# S7CAS-PLEIADES-CARTE-MERE_P06_ETHERNET.net
KiCad netlist of a schematic drawn in Altium Designer
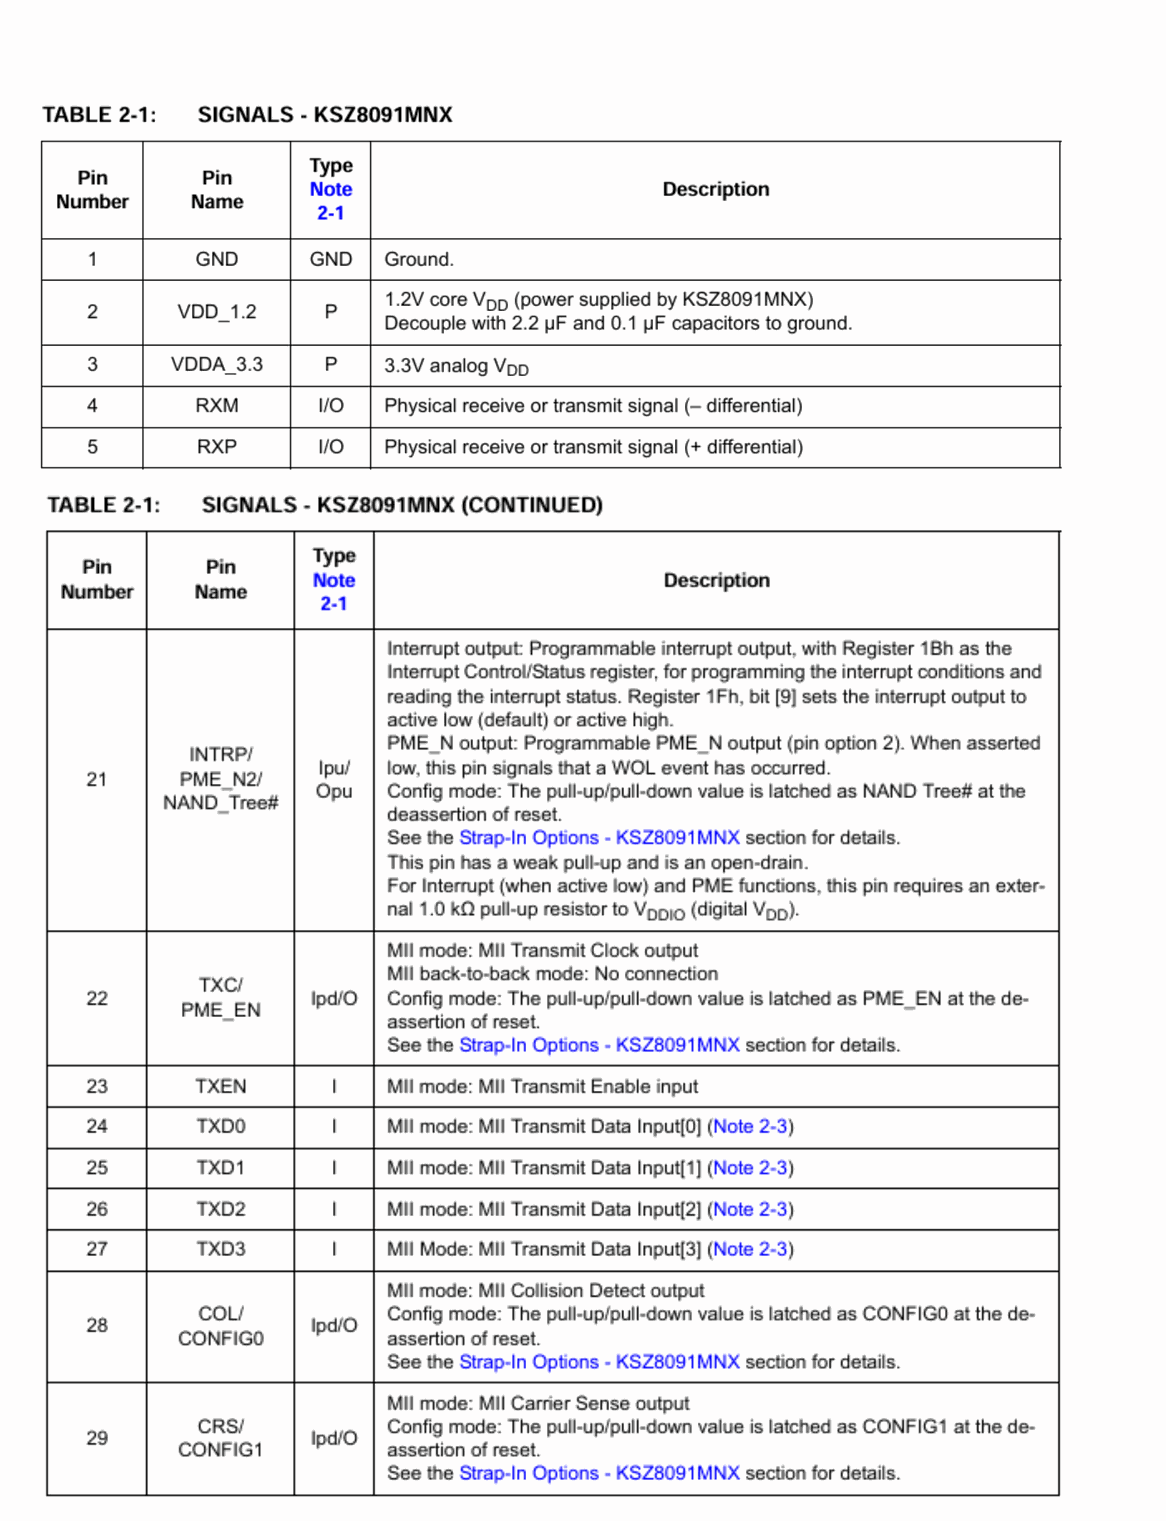
[diagram p0: S7CAS-PLEIADES-CARTE-MERE_P06_ETHERNET.SCHDOC, top left]
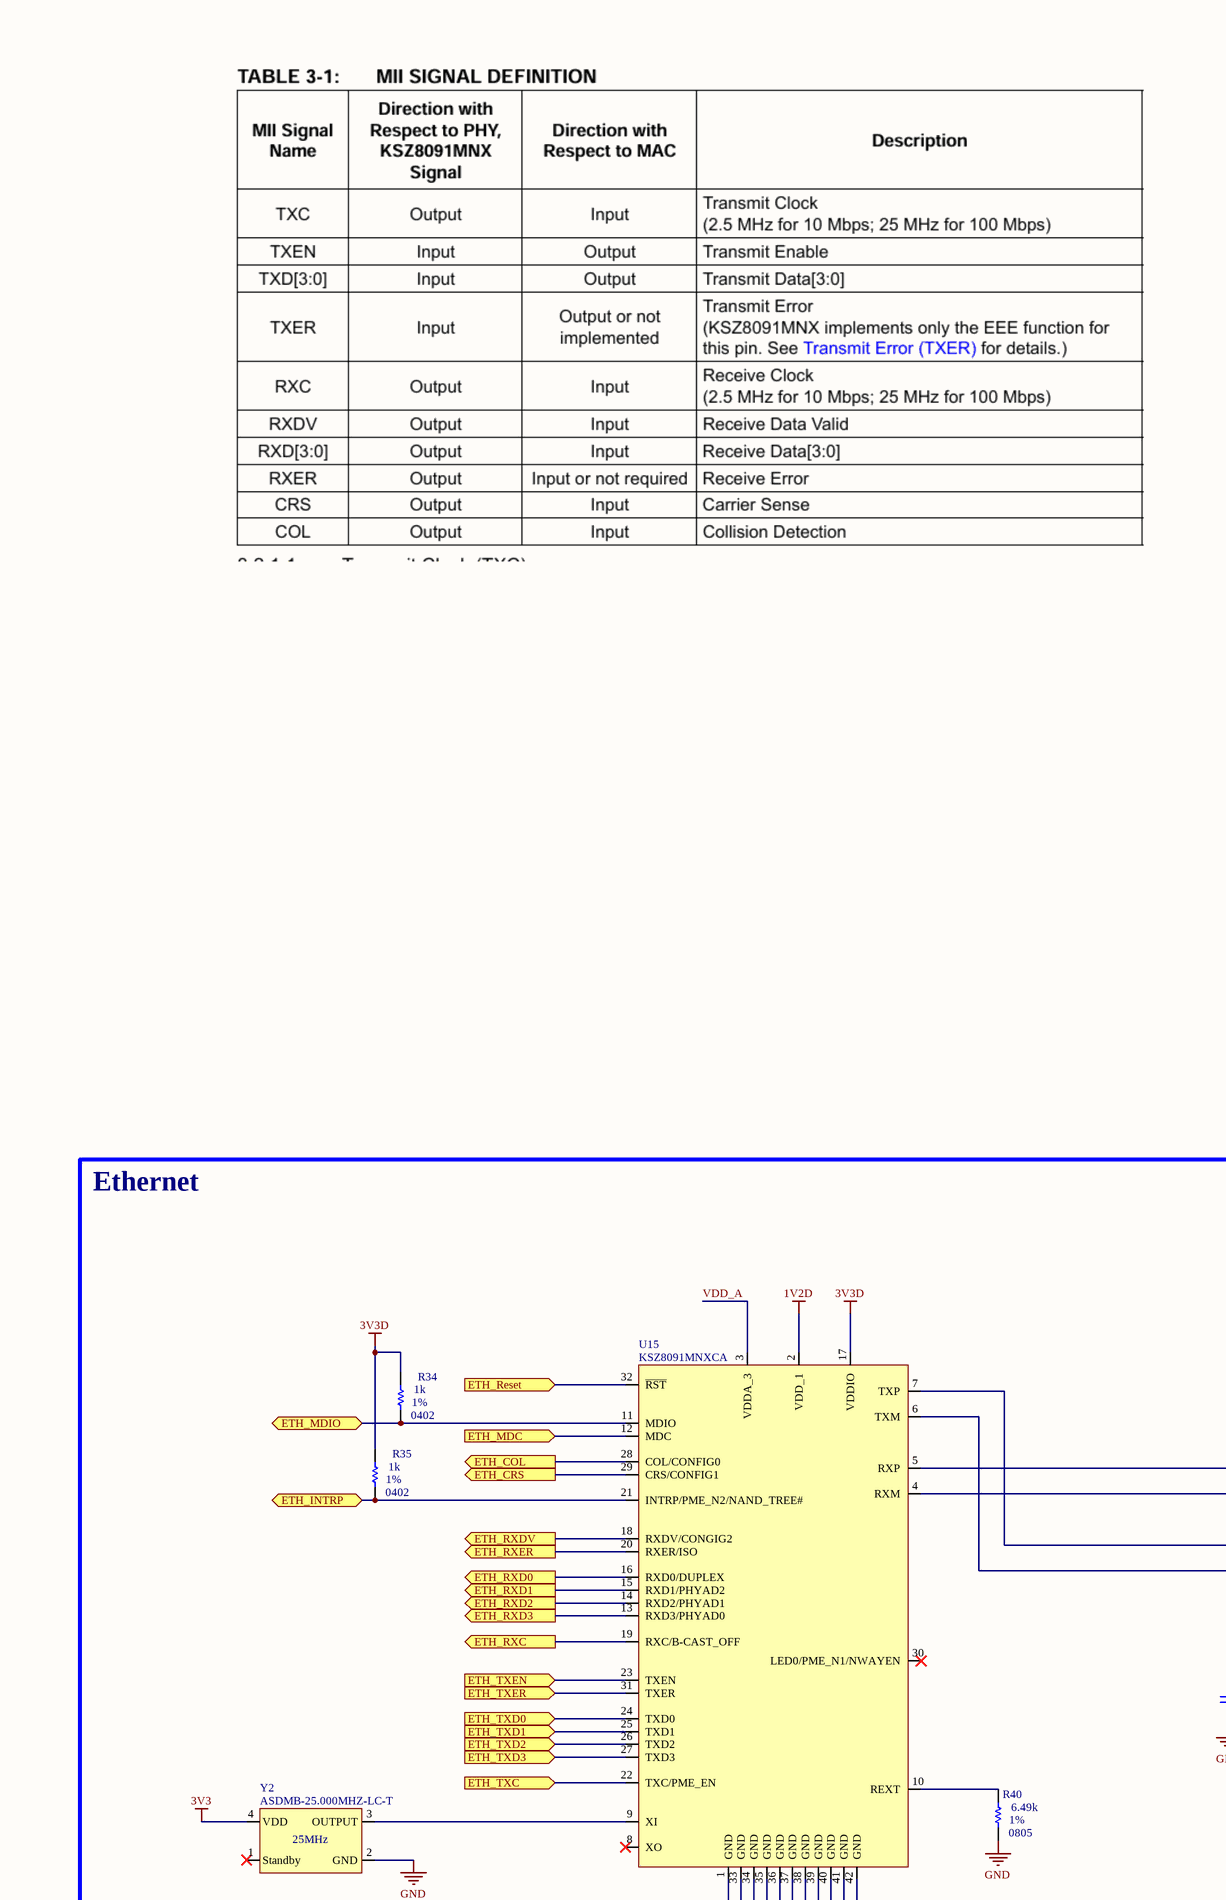
[diagram p1: S7CAS-PLEIADES-CARTE-MERE_P06_ETHERNET.SCHDOC, top middle]
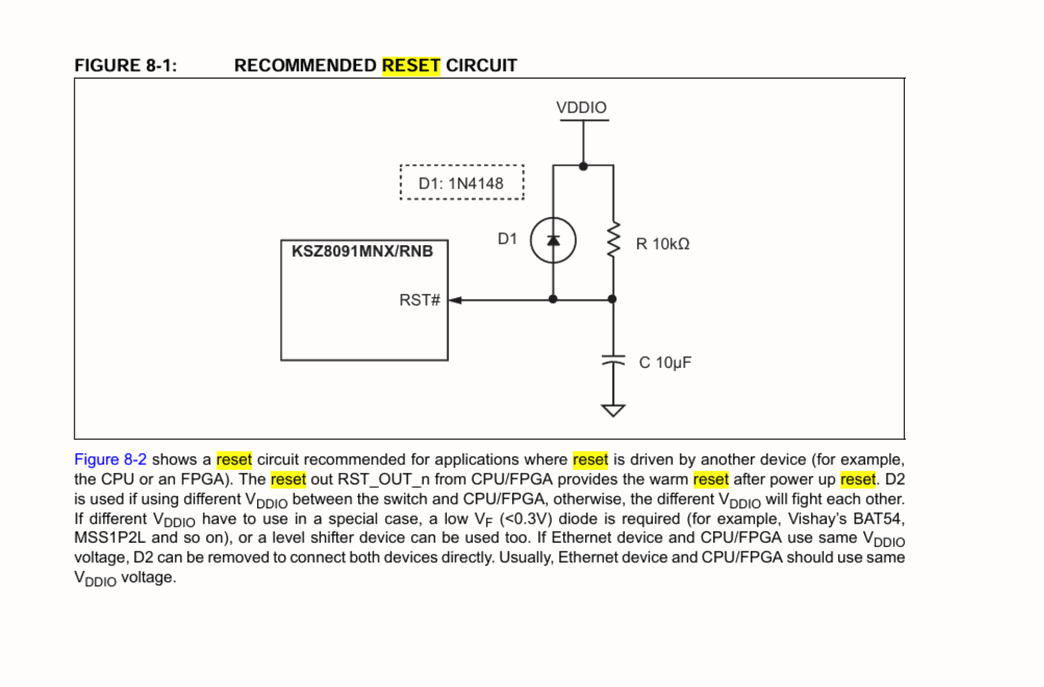
[diagram p2: S7CAS-PLEIADES-CARTE-MERE_P06_ETHERNET.SCHDOC, top right]
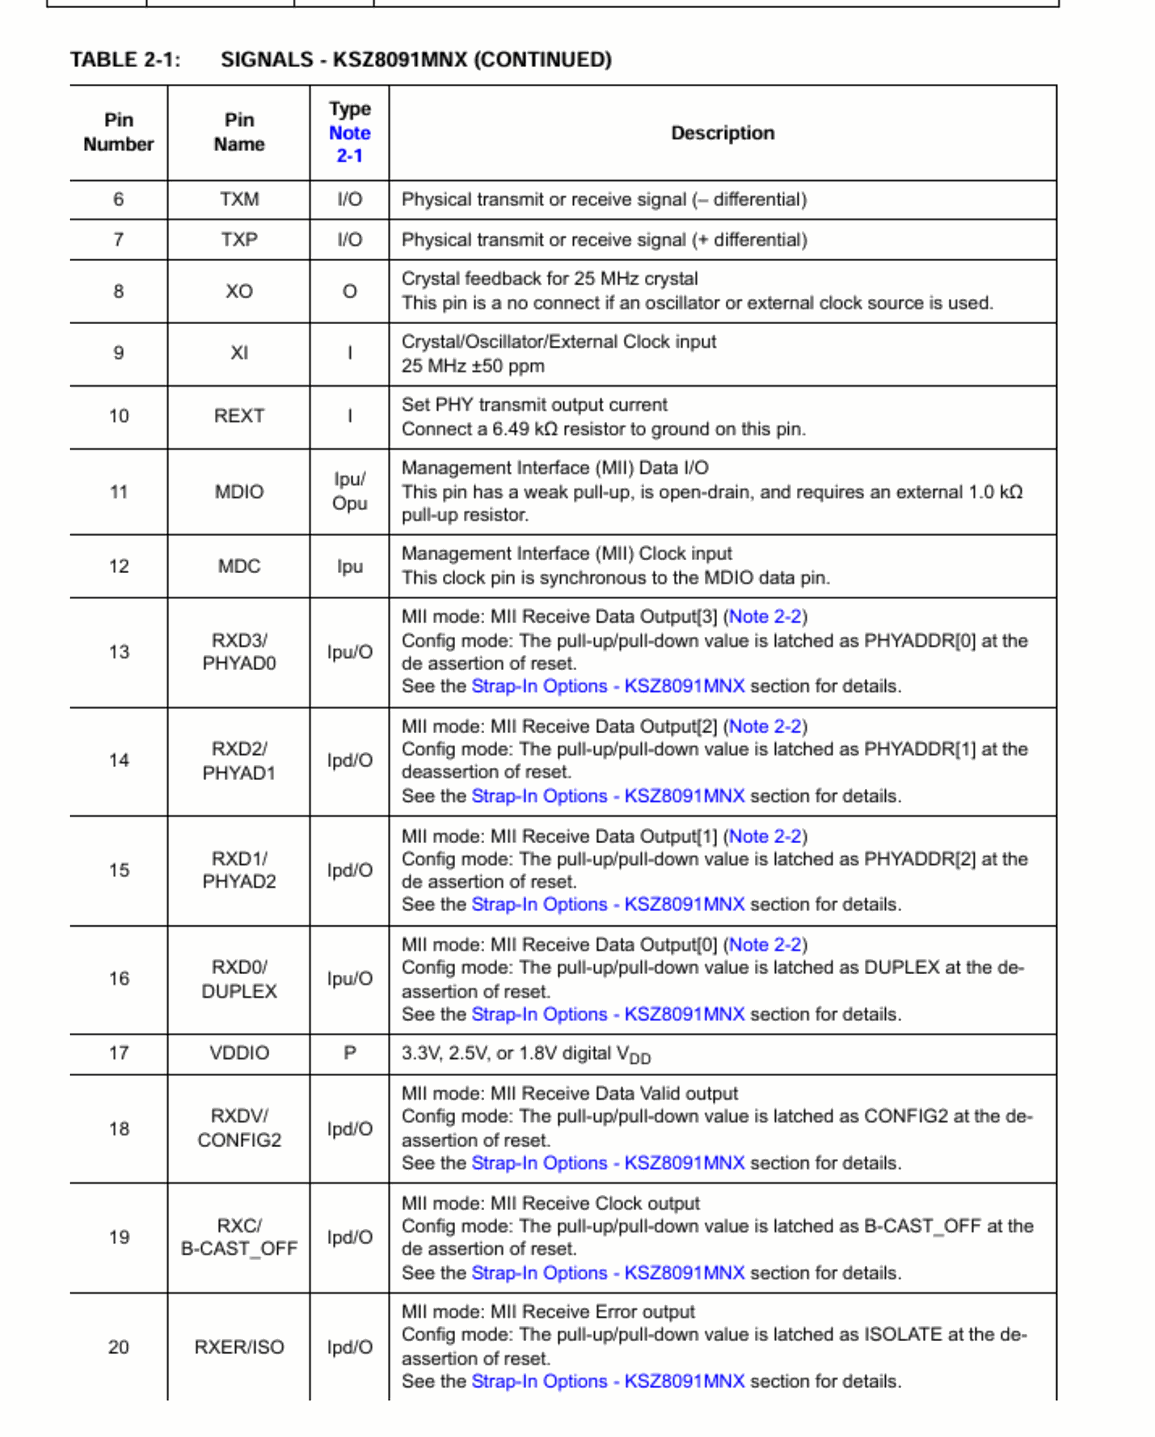
[diagram p3: S7CAS-PLEIADES-CARTE-MERE_P06_ETHERNET.SCHDOC, bottom left]
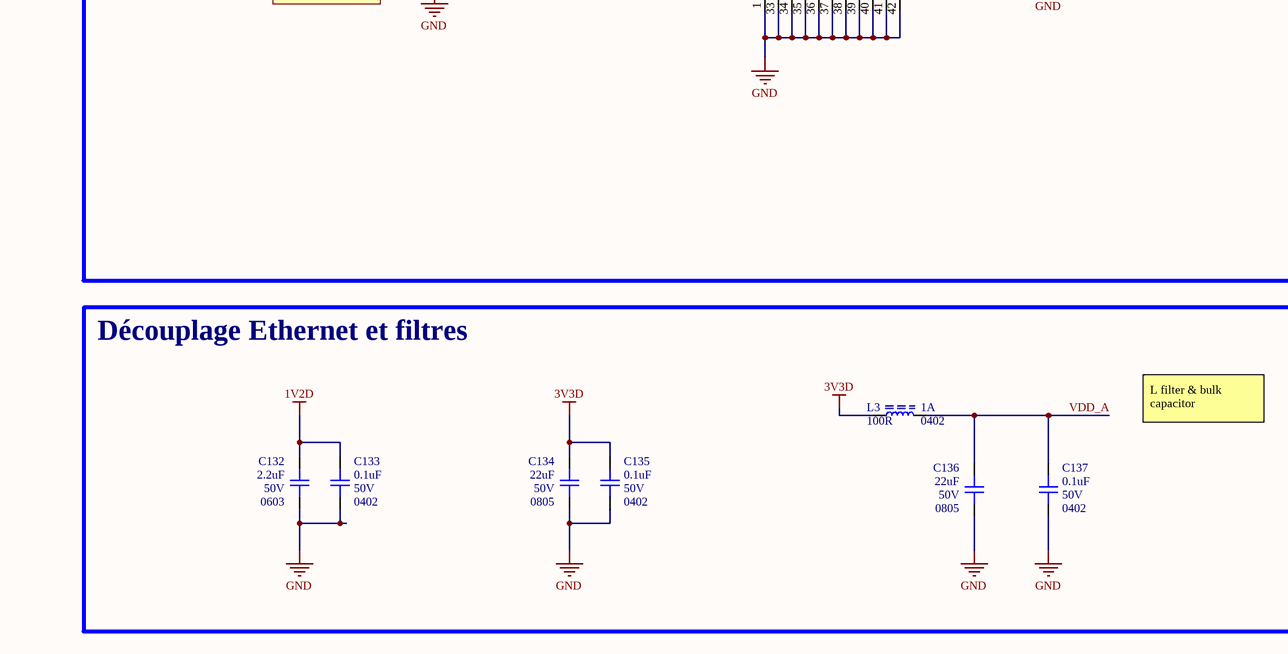
[diagram p4: S7CAS-PLEIADES-CARTE-MERE_P06_ETHERNET.SCHDOC, bottom middle]
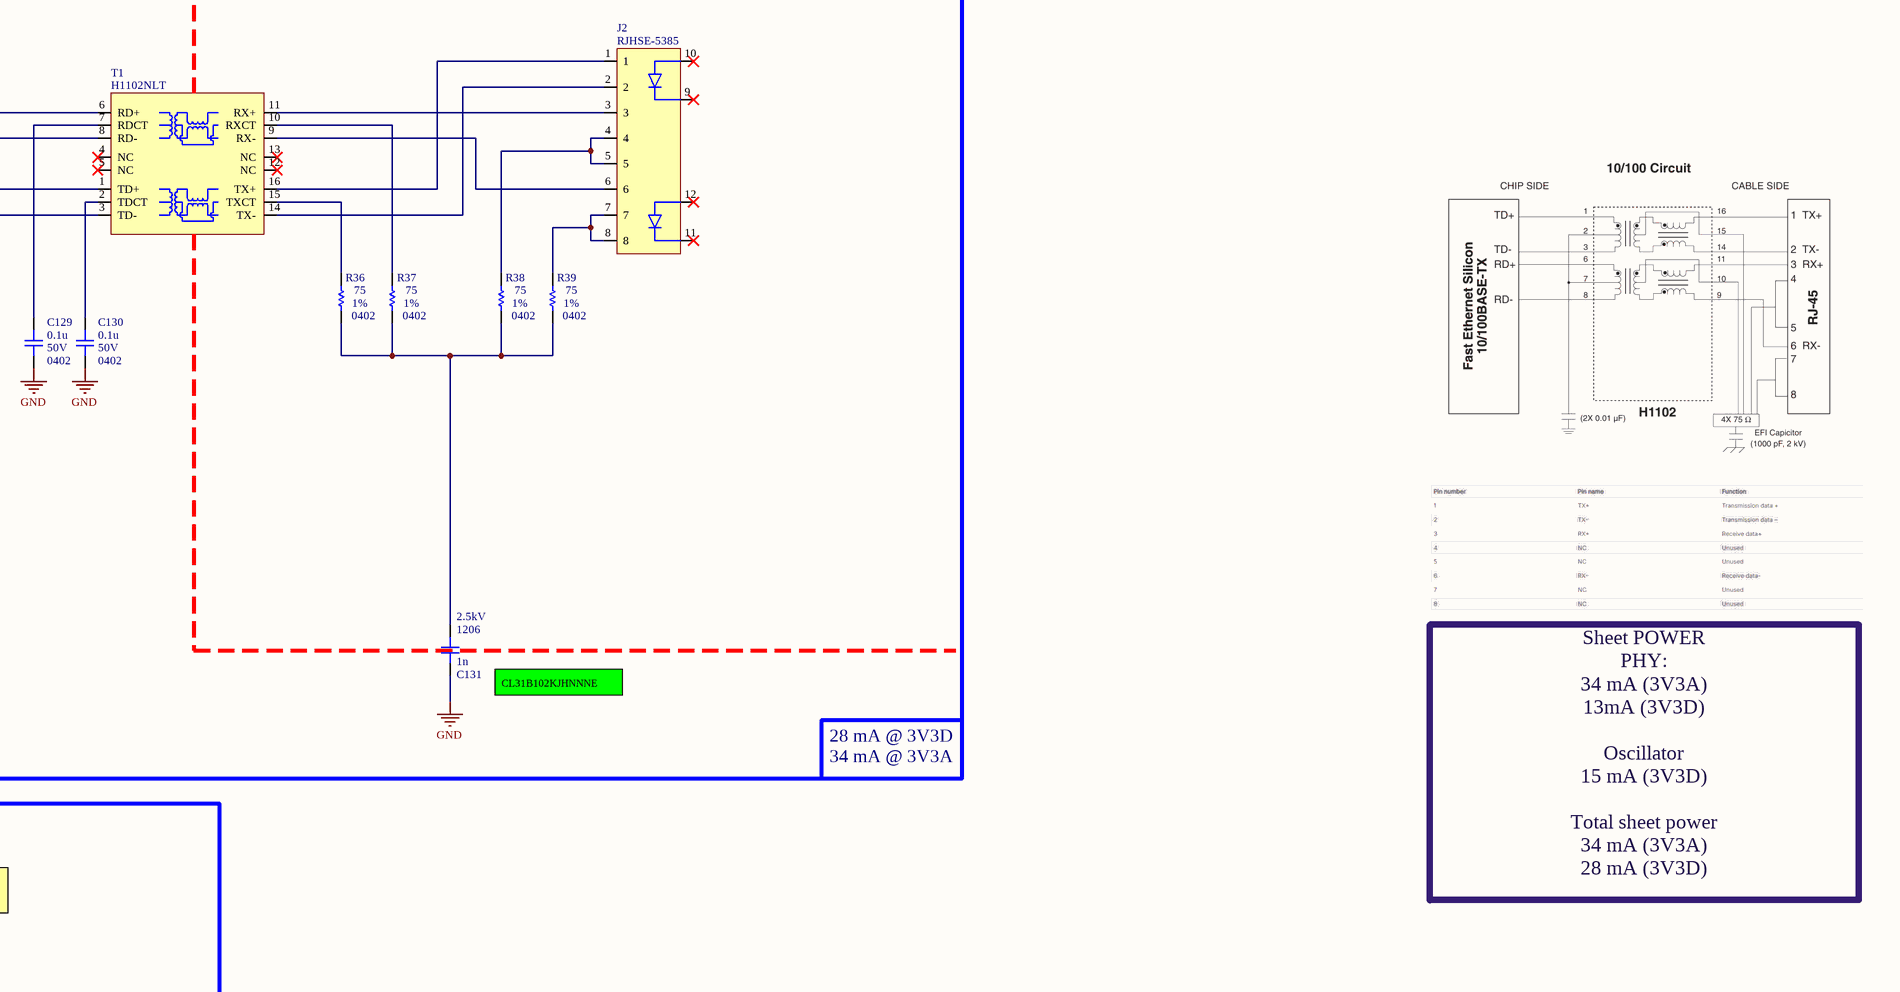
[diagram p5: S7CAS-PLEIADES-CARTE-MERE_P06_ETHERNET.SCHDOC, bottom right]

(export (version "E")
  (design (tool "Eeschema 10.0.6"))
  (components
    (comp (ref "C129")
      (value "0.1u")
      (footprint "CAP_0402")
      (description "CAP - 0402")
      (fields
        (field (name "VOLTAGE") "50V")
        (field (name "PACKAGE") "0402")
        (field (name "CREATEDBY") "Jonathan Bouchard")
      )
      (libsource (lib "s7cas_lib2023") (part "CAP - 0402"))
    )
    (comp (ref "C130")
      (value "0.1u")
      (footprint "CAP_0402")
      (description "CAP - 0402")
      (fields
        (field (name "VOLTAGE") "50V")
        (field (name "PACKAGE") "0402")
        (field (name "CREATEDBY") "Jonathan Bouchard")
      )
      (libsource (lib "s7cas_lib2023") (part "CAP - 0402"))
    )
    (comp (ref "C131")
      (value "1n")
      (footprint "CAP_0402")
      (description "CAP - 0402")
      (fields
        (field (name "VOLTAGE") "2.5kV")
        (field (name "PACKAGE") "1206")
        (field (name "CREATEDBY") "Jonathan Bouchard")
      )
      (libsource (lib "s7cas_lib2023") (part "CAP - 0402"))
    )
    (comp (ref "C132")
      (value "2.2uF")
      (footprint "CAP_0603")
      (description "CAP - 0603")
      (fields
        (field (name "VOLTAGE") "50V")
        (field (name "PACKAGE") "0603")
        (field (name "CREATEDBY") "Jonathan Bouchard")
      )
      (libsource (lib "s7cas_lib2023") (part "CAP - 0603"))
    )
    (comp (ref "C133")
      (value "0.1uF")
      (footprint "CAP_0402")
      (description "CAP - 0402")
      (fields
        (field (name "VOLTAGE") "50V")
        (field (name "PACKAGE") "0402")
        (field (name "CREATEDBY") "Jonathan Bouchard")
      )
      (libsource (lib "s7cas_lib2023") (part "CAP - 0402"))
    )
    (comp (ref "C134")
      (value "22uF")
      (footprint "CAP_0805")
      (description "CAP - 0805")
      (fields
        (field (name "VOLTAGE") "50V")
        (field (name "PACKAGE") "0805")
        (field (name "CREATEDBY") "Jonathan Bouchard")
      )
      (libsource (lib "s7cas_lib2023") (part "CAP - 0805"))
    )
    (comp (ref "C135")
      (value "0.1uF")
      (footprint "CAP_0402")
      (description "CAP - 0402")
      (fields
        (field (name "VOLTAGE") "50V")
        (field (name "PACKAGE") "0402")
        (field (name "CREATEDBY") "Jonathan Bouchard")
      )
      (libsource (lib "s7cas_lib2023") (part "CAP - 0402"))
    )
    (comp (ref "C136")
      (value "22uF")
      (footprint "CAP_0805")
      (description "CAP - 0805")
      (fields
        (field (name "VOLTAGE") "50V")
        (field (name "PACKAGE") "0805")
        (field (name "CREATEDBY") "Jonathan Bouchard")
      )
      (libsource (lib "s7cas_lib2023") (part "CAP - 0805"))
    )
    (comp (ref "C137")
      (value "0.1uF")
      (footprint "CAP_0402")
      (description "CAP - 0402")
      (fields
        (field (name "VOLTAGE") "50V")
        (field (name "PACKAGE") "0402")
        (field (name "CREATEDBY") "Jonathan Bouchard")
      )
      (libsource (lib "s7cas_lib2023") (part "CAP - 0402"))
    )
    (comp (ref "J2")
      (value "RJHSE-5385")
      (footprint "CONN_ETHERNET_RJHSE-5385")
      (description "CONN - MOD JACK RJ45 R/A ETHERNET - TH")
      (fields (field (name "MFG") "Amphenol") (field (name "CREATEDBY") "Jonathan Bouchard"))
      (libsource (lib "s7cas_lib2023") (part "CONN_ETHERNET_RJHSE-5385"))
    )
    (comp (ref "L3")
      (value "100R")
      (footprint "FER_0402")
      (description "FER - 0402")
      (fields
        (field (name "CURRENT") "1A")
        (field (name "PACKAGE") "0402")
        (field (name "CREATEDBY") "Jonathan Bouchard")
      )
      (libsource (lib "s7cas_lib2023") (part "FER - 0402"))
    )
    (comp (ref "R34")
      (value "1k")
      (footprint "RES_0402")
      (description "RES - 0402")
      (fields
        (field (name "VOLTAGE") "50V")
        (field (name "POWER") "1/16W")
        (field (name "PACKAGE") "0402")
        (field (name "PRECISION") "1%")
        (field (name "CREATEDBY") "Jonathan Bouchard")
      )
      (libsource (lib "s7cas_lib2023") (part "RES - 0402"))
    )
    (comp (ref "R35")
      (value "1k")
      (footprint "RES_0402")
      (description "RES - 0402")
      (fields
        (field (name "VOLTAGE") "50V")
        (field (name "POWER") "1/16W")
        (field (name "PACKAGE") "0402")
        (field (name "PRECISION") "1%")
        (field (name "CREATEDBY") "Jonathan Bouchard")
      )
      (libsource (lib "s7cas_lib2023") (part "RES - 0402"))
    )
    (comp (ref "R36")
      (value "75")
      (footprint "RES_0402")
      (description "RES - 0402")
      (fields
        (field (name "VOLTAGE") "50V")
        (field (name "POWER") "1/16W")
        (field (name "PACKAGE") "0402")
        (field (name "PRECISION") "1%")
        (field (name "CREATEDBY") "Jonathan Bouchard")
      )
      (libsource (lib "s7cas_lib2023") (part "RES - 0402"))
    )
    (comp (ref "R37")
      (value "75")
      (footprint "RES_0402")
      (description "RES - 0402")
      (fields
        (field (name "VOLTAGE") "50V")
        (field (name "POWER") "1/16W")
        (field (name "PACKAGE") "0402")
        (field (name "PRECISION") "1%")
        (field (name "CREATEDBY") "Jonathan Bouchard")
      )
      (libsource (lib "s7cas_lib2023") (part "RES - 0402"))
    )
    (comp (ref "R38")
      (value "75")
      (footprint "RES_0402")
      (description "RES - 0402")
      (fields
        (field (name "VOLTAGE") "50V")
        (field (name "POWER") "1/16W")
        (field (name "PACKAGE") "0402")
        (field (name "PRECISION") "1%")
        (field (name "CREATEDBY") "Jonathan Bouchard")
      )
      (libsource (lib "s7cas_lib2023") (part "RES - 0402"))
    )
    (comp (ref "R39")
      (value "75")
      (footprint "RES_0402")
      (description "RES - 0402")
      (fields
        (field (name "VOLTAGE") "50V")
        (field (name "POWER") "1/16W")
        (field (name "PACKAGE") "0402")
        (field (name "PRECISION") "1%")
        (field (name "CREATEDBY") "Jonathan Bouchard")
      )
      (libsource (lib "s7cas_lib2023") (part "RES - 0402"))
    )
    (comp (ref "R40")
      (value "6.49k")
      (footprint "RES_0805")
      (description "RES - 0805")
      (fields
        (field (name "PACKAGE") "0805")
        (field (name "PRECISION") "1%")
        (field (name "CREATEDBY") "Jonathan Bouchard")
      )
      (libsource (lib "s7cas_lib2023") (part "RES - 0805"))
    )
    (comp (ref "T1")
      (value "H1102NLT")
      (footprint "TRANSFO_H1102NLT")
      (description "TRANSFO - ETHERNET 10/100B-TX - SMD-16")
      (fields (field (name "MFG") "Pulse Eng.") (field (name "CREATEDBY") "Jonathan Bouchard"))
      (libsource (lib "s7cas_lib2023") (part "TRANSFO_H1102NLT"))
    )
    (comp (ref "U15")
      (value "KSZ8091MNXCA")
      (footprint "COM_ETH_PHY_KSZ8091MNXCA")
      (description "COM - ETHERNET PHY 10/100 - QFN-32")
      (fields
        (field (name "VOLTAGE") "1.8V, 2.5V, 3.3V")
        (field (name "MFG") "Micrel")
        (field (name "CREATEDBY") "Jonathan Bouchard")
      )
      (libsource (lib "s7cas_lib2023") (part "COM_ETH_PHY_KSZ8091MNXCA"))
    )
    (comp (ref "Y2")
      (value "ASDMB-25.000MHZ-LC-T")
      (footprint "OSC_ASDMB-25.000MHZ-LC-T")
      (description "OSC - 25MHz XO (Standard) LVCMOS - 4-SMD, No Lead")
      (fields
        (field (name "TOLERANCE") "±50ppm")
        (field (name "CREATEDBY/DATE") "Joël Lemay 2019-03-29")
        (field (name "VERIFIEDBY") "C. Paulin - 29 mai 2019")
      )
      (libsource (lib "s7cas_lib2023") (part "OSC_ASDMB-25.000MHZ-LC-T"))
    )
  )
  (nets
    (net (code "1") (name "/ETH_COL") (class "Default")
      (node (ref "U15") (pin "28") (pinfunction "COL/CONFIG0_28") (pintype "passive"))
    )
    (net (code "2") (name "/ETH_CRS") (class "Default")
      (node (ref "U15") (pin "29") (pinfunction "CRS/CONFIG1_29") (pintype "passive"))
    )
    (net (code "3") (name "/ETH_INTRP") (class "Default")
      (node (ref "R35") (pin "1") (pinfunction "1_1") (pintype "passive"))
      (node (ref "U15") (pin "21") (pinfunction "INTRP/PME_N2/NAND_TREE#_21") (pintype "passive"))
    )
    (net (code "4") (name "/ETH_MDC") (class "Default")
      (node (ref "U15") (pin "12") (pinfunction "MDC_12") (pintype "passive"))
    )
    (net (code "5") (name "/ETH_MDIO") (class "Default")
      (node (ref "R34") (pin "1") (pinfunction "1_1") (pintype "passive"))
      (node (ref "U15") (pin "11") (pinfunction "MDIO_11") (pintype "passive"))
    )
    (net (code "6") (name "/ETH_RXC") (class "Default")
      (node (ref "U15") (pin "19") (pinfunction "RXC/B-CAST_OFF_19") (pintype "passive"))
    )
    (net (code "7") (name "/ETH_RXD0") (class "Default")
      (node (ref "U15") (pin "16") (pinfunction "RXD0/DUPLEX_16") (pintype "passive"))
    )
    (net (code "8") (name "/ETH_RXD1") (class "Default")
      (node (ref "U15") (pin "15") (pinfunction "RXD1/PHYAD2_15") (pintype "passive"))
    )
    (net (code "9") (name "/ETH_RXD2") (class "Default")
      (node (ref "U15") (pin "14") (pinfunction "RXD2/PHYAD1_14") (pintype "passive"))
    )
    (net (code "10") (name "/ETH_RXD3") (class "Default")
      (node (ref "U15") (pin "13") (pinfunction "RXD3/PHYAD0_13") (pintype "passive"))
    )
    (net (code "11") (name "/ETH_RXDV") (class "Default")
      (node (ref "U15") (pin "18") (pinfunction "RXDV/CONGIG2_18") (pintype "passive"))
    )
    (net (code "12") (name "/ETH_RXER") (class "Default")
      (node (ref "U15") (pin "20") (pinfunction "RXER/ISO_20") (pintype "passive"))
    )
    (net (code "13") (name "/ETH_Reset") (class "Default")
      (node (ref "U15") (pin "32") (pinfunction "RST_32") (pintype "passive"))
    )
    (net (code "14") (name "/ETH_TXC") (class "Default")
      (node (ref "U15") (pin "22") (pinfunction "TXC/PME_EN_22") (pintype "passive"))
    )
    (net (code "15") (name "/ETH_TXD0") (class "Default")
      (node (ref "U15") (pin "24") (pinfunction "TXD0_24") (pintype "passive"))
    )
    (net (code "16") (name "/ETH_TXD1") (class "Default")
      (node (ref "U15") (pin "25") (pinfunction "TXD1_25") (pintype "passive"))
    )
    (net (code "17") (name "/ETH_TXD2") (class "Default")
      (node (ref "U15") (pin "26") (pinfunction "TXD2_26") (pintype "passive"))
    )
    (net (code "18") (name "/ETH_TXD3") (class "Default")
      (node (ref "U15") (pin "27") (pinfunction "TXD3_27") (pintype "passive"))
    )
    (net (code "19") (name "/ETH_TXEN") (class "Default")
      (node (ref "U15") (pin "23") (pinfunction "TXEN_23") (pintype "passive"))
    )
    (net (code "20") (name "/ETH_TXER") (class "Default")
      (node (ref "U15") (pin "31") (pinfunction "TXER_31") (pintype "passive"))
    )
    (net (code "21") (name "/VDD_A") (class "Default")
      (node (ref "C136") (pin "2") (pinfunction "2_2") (pintype "passive"))
      (node (ref "C137") (pin "2") (pinfunction "2_2") (pintype "passive"))
      (node (ref "L3") (pin "1") (pinfunction "1_1") (pintype "passive"))
      (node (ref "U15") (pin "3") (pinfunction "VDDA_3_3") (pintype "power_in"))
    )
    (net (code "22") (name "1V2D") (class "Default")
      (node (ref "C132") (pin "2") (pinfunction "2_2") (pintype "passive"))
      (node (ref "C133") (pin "2") (pinfunction "2_2") (pintype "passive"))
      (node (ref "U15") (pin "2") (pinfunction "VDD_1_2") (pintype "power_in"))
    )
    (net (code "23") (name "3V3") (class "Default")
      (node (ref "Y2") (pin "4") (pinfunction "VDD_4") (pintype "passive"))
    )
    (net (code "24") (name "3V3D") (class "Default")
      (node (ref "C134") (pin "2") (pinfunction "2_2") (pintype "passive"))
      (node (ref "C135") (pin "2") (pinfunction "2_2") (pintype "passive"))
      (node (ref "L3") (pin "2") (pinfunction "2_2") (pintype "passive"))
      (node (ref "R34") (pin "2") (pinfunction "2_2") (pintype "passive"))
      (node (ref "R35") (pin "2") (pinfunction "2_2") (pintype "passive"))
      (node (ref "U15") (pin "17") (pinfunction "VDDIO_17") (pintype "power_in"))
    )
    (net (code "25") (name "GND") (class "Default")
      (node (ref "C129") (pin "1") (pinfunction "1_1") (pintype "passive"))
      (node (ref "C130") (pin "1") (pinfunction "1_1") (pintype "passive"))
      (node (ref "C131") (pin "2") (pinfunction "2_2") (pintype "passive"))
      (node (ref "C132") (pin "1") (pinfunction "1_1") (pintype "passive"))
      (node (ref "C133") (pin "1") (pinfunction "1_1") (pintype "passive"))
      (node (ref "C134") (pin "1") (pinfunction "1_1") (pintype "passive"))
      (node (ref "C135") (pin "1") (pinfunction "1_1") (pintype "passive"))
      (node (ref "C136") (pin "1") (pinfunction "1_1") (pintype "passive"))
      (node (ref "C137") (pin "1") (pinfunction "1_1") (pintype "passive"))
      (node (ref "R40") (pin "1") (pinfunction "1_1") (pintype "passive"))
      (node (ref "U15") (pin "1") (pinfunction "GND_1") (pintype "passive"))
      (node (ref "U15") (pin "33") (pinfunction "GND_33") (pintype "passive"))
      (node (ref "U15") (pin "34") (pinfunction "GND_34") (pintype "passive"))
      (node (ref "U15") (pin "35") (pinfunction "GND_35") (pintype "passive"))
      (node (ref "U15") (pin "36") (pinfunction "GND_36") (pintype "passive"))
      (node (ref "U15") (pin "37") (pinfunction "GND_37") (pintype "passive"))
      (node (ref "U15") (pin "38") (pinfunction "GND_38") (pintype "passive"))
      (node (ref "U15") (pin "39") (pinfunction "GND_39") (pintype "passive"))
      (node (ref "U15") (pin "40") (pinfunction "GND_40") (pintype "passive"))
      (node (ref "U15") (pin "41") (pinfunction "GND_41") (pintype "passive"))
      (node (ref "U15") (pin "42") (pinfunction "GND_42") (pintype "passive"))
      (node (ref "Y2") (pin "2") (pinfunction "GND_2") (pintype "passive"))
    )
    (net (code "26") (name "Net-(C131-Pad1)") (class "Default")
      (node (ref "C131") (pin "1") (pinfunction "1_1") (pintype "passive"))
      (node (ref "R36") (pin "1") (pinfunction "1_1") (pintype "passive"))
      (node (ref "R37") (pin "1") (pinfunction "1_1") (pintype "passive"))
      (node (ref "R38") (pin "1") (pinfunction "1_1") (pintype "passive"))
      (node (ref "R39") (pin "1") (pinfunction "1_1") (pintype "passive"))
    )
    (net (code "27") (name "Net-(J2-Pad4)") (class "Default")
      (node (ref "J2") (pin "4") (pinfunction "4_4") (pintype "passive"))
      (node (ref "J2") (pin "5") (pinfunction "5_5") (pintype "passive"))
      (node (ref "R38") (pin "2") (pinfunction "2_2") (pintype "passive"))
    )
    (net (code "28") (name "Net-(J2-Pad7)") (class "Default")
      (node (ref "J2") (pin "7") (pinfunction "7_7") (pintype "passive"))
      (node (ref "J2") (pin "8") (pinfunction "8_8") (pintype "passive"))
      (node (ref "R39") (pin "2") (pinfunction "2_2") (pintype "passive"))
    )
    (net (code "29") (name "Net-(T1-RD+)") (class "Default")
      (node (ref "T1") (pin "6") (pinfunction "RD+_6") (pintype "passive"))
      (node (ref "U15") (pin "5") (pinfunction "RXP_5") (pintype "passive"))
    )
    (net (code "30") (name "Net-(T1-RD-)") (class "Default")
      (node (ref "T1") (pin "8") (pinfunction "RD-_8") (pintype "passive"))
      (node (ref "U15") (pin "4") (pinfunction "RXM_4") (pintype "passive"))
    )
    (net (code "31") (name "Net-(T1-RDCT)") (class "Default")
      (node (ref "C129") (pin "2") (pinfunction "2_2") (pintype "passive"))
      (node (ref "T1") (pin "7") (pinfunction "RDCT_7") (pintype "passive"))
    )
    (net (code "32") (name "Net-(T1-RX+)") (class "Default")
      (node (ref "J2") (pin "3") (pinfunction "3_3") (pintype "passive"))
      (node (ref "T1") (pin "11") (pinfunction "RX+_11") (pintype "passive"))
    )
    (net (code "33") (name "Net-(T1-RX-)") (class "Default")
      (node (ref "J2") (pin "6") (pinfunction "6_6") (pintype "passive"))
      (node (ref "T1") (pin "9") (pinfunction "RX-_9") (pintype "passive"))
    )
    (net (code "34") (name "Net-(T1-RXCT)") (class "Default")
      (node (ref "R37") (pin "2") (pinfunction "2_2") (pintype "passive"))
      (node (ref "T1") (pin "10") (pinfunction "RXCT_10") (pintype "passive"))
    )
    (net (code "35") (name "Net-(T1-TD+)") (class "Default")
      (node (ref "T1") (pin "1") (pinfunction "TD+_1") (pintype "passive"))
      (node (ref "U15") (pin "7") (pinfunction "TXP_7") (pintype "passive"))
    )
    (net (code "36") (name "Net-(T1-TD-)") (class "Default")
      (node (ref "T1") (pin "3") (pinfunction "TD-_3") (pintype "passive"))
      (node (ref "U15") (pin "6") (pinfunction "TXM_6") (pintype "passive"))
    )
    (net (code "37") (name "Net-(T1-TDCT)") (class "Default")
      (node (ref "C130") (pin "2") (pinfunction "2_2") (pintype "passive"))
      (node (ref "T1") (pin "2") (pinfunction "TDCT_2") (pintype "passive"))
    )
    (net (code "38") (name "Net-(T1-TX+)") (class "Default")
      (node (ref "J2") (pin "1") (pinfunction "1_1") (pintype "passive"))
      (node (ref "T1") (pin "16") (pinfunction "TX+_16") (pintype "passive"))
    )
    (net (code "39") (name "Net-(T1-TX-)") (class "Default")
      (node (ref "J2") (pin "2") (pinfunction "2_2") (pintype "passive"))
      (node (ref "T1") (pin "14") (pinfunction "TX-_14") (pintype "passive"))
    )
    (net (code "40") (name "Net-(T1-TXCT)") (class "Default")
      (node (ref "R36") (pin "2") (pinfunction "2_2") (pintype "passive"))
      (node (ref "T1") (pin "15") (pinfunction "TXCT_15") (pintype "passive"))
    )
    (net (code "41") (name "Net-(U15-REXT)") (class "Default")
      (node (ref "R40") (pin "2") (pinfunction "2_2") (pintype "passive"))
      (node (ref "U15") (pin "10") (pinfunction "REXT_10") (pintype "passive"))
    )
    (net (code "42") (name "Net-(U15-XI)") (class "Default")
      (node (ref "U15") (pin "9") (pinfunction "XI_9") (pintype "passive"))
      (node (ref "Y2") (pin "3") (pinfunction "OUTPUT_3") (pintype "passive"))
    )
    (net (code "43") (name "unconnected-(J2-LED1_A-Pad10)") (class "Default")
      (node (ref "J2") (pin "10") (pinfunction "LED1_A_10") (pintype "passive+no_connect"))
    )
    (net (code "44") (name "unconnected-(J2-LED1_K-Pad9)") (class "Default")
      (node (ref "J2") (pin "9") (pinfunction "LED1_K_9") (pintype "passive+no_connect"))
    )
    (net (code "45") (name "unconnected-(J2-LED2_A-Pad12)") (class "Default")
      (node (ref "J2") (pin "12") (pinfunction "LED2_A_12") (pintype "passive+no_connect"))
    )
    (net (code "46") (name "unconnected-(J2-LED2_K-Pad11)") (class "Default")
      (node (ref "J2") (pin "11") (pinfunction "LED2_K_11") (pintype "passive+no_connect"))
    )
    (net (code "47") (name "unconnected-(T1-NC-Pad4)") (class "Default")
      (node (ref "T1") (pin "4") (pinfunction "NC_4") (pintype "passive+no_connect"))
    )
    (net (code "48") (name "unconnected-(T1-NC-Pad5)") (class "Default")
      (node (ref "T1") (pin "5") (pinfunction "NC_5") (pintype "passive+no_connect"))
    )
    (net (code "49") (name "unconnected-(T1-NC-Pad12)") (class "Default")
      (node (ref "T1") (pin "12") (pinfunction "NC_12") (pintype "passive+no_connect"))
    )
    (net (code "50") (name "unconnected-(T1-NC-Pad13)") (class "Default")
      (node (ref "T1") (pin "13") (pinfunction "NC_13") (pintype "passive+no_connect"))
    )
    (net (code "51") (name "unconnected-(U15-LED0{slash}PME_N1{slash}NWAYEN-Pad30)") (class "Default")
      (node (ref "U15") (pin "30") (pinfunction "LED0/PME_N1/NWAYEN_30") (pintype "passive+no_connect"))
    )
    (net (code "52") (name "unconnected-(U15-XO-Pad8)") (class "Default")
      (node (ref "U15") (pin "8") (pinfunction "XO_8") (pintype "passive+no_connect"))
    )
    (net (code "53") (name "unconnected-(Y2-Standby-Pad1)") (class "Default")
      (node (ref "Y2") (pin "1") (pinfunction "Standby_1") (pintype "passive+no_connect"))
    )
  )
)
